# Placa_ATMEL_2019_v2.net
KiCad netlist of a schematic drawn in EAGLE
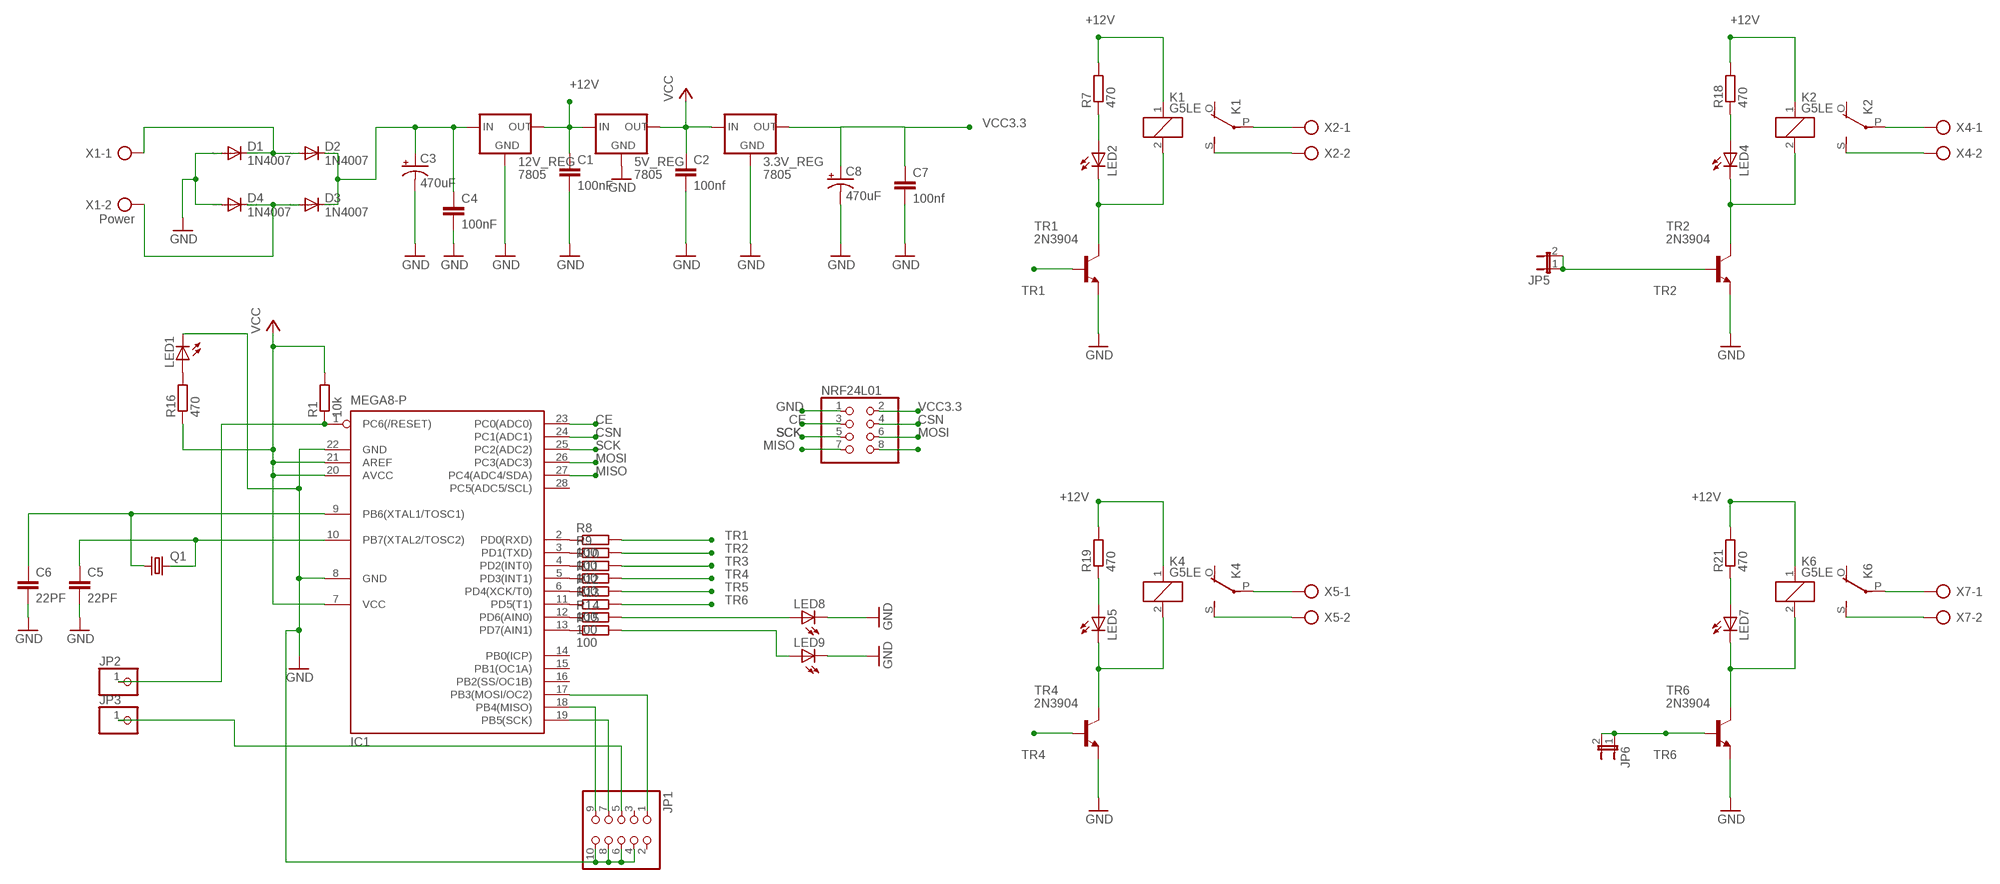
[diagram p0: schematic, sheet 1]

(export (version "E")
  (design (tool "Eeschema 10.0.6"))
  (components
    (comp (ref "3.3V_REG")
      (value "7805")
      (footprint "eagle-import:78XXL")
      (libsource (lib "eagle-import") (part "78XXL"))
    )
    (comp (ref "5V_REG")
      (value "7805")
      (footprint "eagle-import:78XXL")
      (libsource (lib "eagle-import") (part "78XXL"))
    )
    (comp (ref "12V_REG")
      (value "7805")
      (footprint "eagle-import:78XXL")
      (libsource (lib "eagle-import") (part "78XXL"))
    )
    (comp (ref "C1")
      (value "100nF")
      (footprint "eagle-import:C050-025X075")
      (libsource (lib "eagle-import") (part "C-EU050-025X075"))
    )
    (comp (ref "C2")
      (value "100nf")
      (footprint "eagle-import:C050-025X075")
      (libsource (lib "eagle-import") (part "C-EU050-025X075"))
    )
    (comp (ref "C3")
      (value "470uF")
      (footprint "eagle-import:E7,5-16")
      (libsource (lib "eagle-import") (part "CPOL-USE7.5-16"))
    )
    (comp (ref "C4")
      (value "100nF")
      (footprint "eagle-import:C050-025X075")
      (libsource (lib "eagle-import") (part "C-EU050-025X075"))
    )
    (comp (ref "C5")
      (value "22PF")
      (footprint "eagle-import:C050-024X044")
      (libsource (lib "eagle-import") (part "C-EU050-024X044"))
    )
    (comp (ref "C6")
      (value "22PF")
      (footprint "eagle-import:C050-024X044")
      (libsource (lib "eagle-import") (part "C-EU050-024X044"))
    )
    (comp (ref "C7")
      (value "100nf")
      (footprint "eagle-import:C050-025X075")
      (libsource (lib "eagle-import") (part "C-EU050-025X075"))
    )
    (comp (ref "C8")
      (value "470uF")
      (footprint "eagle-import:E7,5-16")
      (libsource (lib "eagle-import") (part "CPOL-USE7.5-16"))
    )
    (comp (ref "D1")
      (value "1N4007")
      (footprint "eagle-import:DO41-10")
      (libsource (lib "eagle-import") (part "1N4004"))
    )
    (comp (ref "D2")
      (value "1N4007")
      (footprint "eagle-import:DO41-10")
      (libsource (lib "eagle-import") (part "1N4004"))
    )
    (comp (ref "D3")
      (value "1N4007")
      (footprint "eagle-import:DO41-10")
      (libsource (lib "eagle-import") (part "1N4004"))
    )
    (comp (ref "D4")
      (value "1N4007")
      (footprint "eagle-import:DO41-10")
      (libsource (lib "eagle-import") (part "1N4004"))
    )
    (comp (ref "IC1")
      (value "MEGA8-P")
      (footprint "eagle-import:DIL28-3")
      (libsource (lib "eagle-import") (part "MEGA8-P"))
    )
    (comp (ref "JP1")
      (value "PINHD-2X5")
      (footprint "eagle-import:2X05")
      (libsource (lib "eagle-import") (part "PINHD-2X5"))
    )
    (comp (ref "JP2")
      (value "PINHD-1X1")
      (footprint "eagle-import:1X01")
      (libsource (lib "eagle-import") (part "PINHD-1X1"))
    )
    (comp (ref "JP3")
      (value "PINHD-1X1")
      (footprint "eagle-import:1X01")
      (libsource (lib "eagle-import") (part "PINHD-1X1"))
    )
    (comp (ref "JP5")
      (value "JP1E")
      (footprint "eagle-import:JP1")
      (libsource (lib "eagle-import") (part "JP1E"))
    )
    (comp (ref "JP6")
      (value "JP1E")
      (footprint "eagle-import:JP1")
      (libsource (lib "eagle-import") (part "JP1E"))
    )
    (comp (ref "K1")
      (value "G5LE")
      (footprint "eagle-import:G5LE")
      (libsource (lib "eagle-import") (part "G5LE"))
    )
    (comp (ref "K2")
      (value "G5LE")
      (footprint "eagle-import:G5LE")
      (libsource (lib "eagle-import") (part "G5LE"))
    )
    (comp (ref "K4")
      (value "G5LE")
      (footprint "eagle-import:G5LE")
      (libsource (lib "eagle-import") (part "G5LE"))
    )
    (comp (ref "K6")
      (value "G5LE")
      (footprint "eagle-import:G5LE")
      (libsource (lib "eagle-import") (part "G5LE"))
    )
    (comp (ref "LED1")
      (value "LED5MM")
      (footprint "eagle-import:LED5MM")
      (libsource (lib "eagle-import") (part "LED5MM"))
    )
    (comp (ref "LED2")
      (value "LED5MM")
      (footprint "eagle-import:LED5MM")
      (libsource (lib "eagle-import") (part "LED5MM"))
    )
    (comp (ref "LED4")
      (value "LED5MM")
      (footprint "eagle-import:LED5MM")
      (libsource (lib "eagle-import") (part "LED5MM"))
    )
    (comp (ref "LED5")
      (value "LED5MM")
      (footprint "eagle-import:LED5MM")
      (libsource (lib "eagle-import") (part "LED5MM"))
    )
    (comp (ref "LED7")
      (value "LED5MM")
      (footprint "eagle-import:LED5MM")
      (libsource (lib "eagle-import") (part "LED5MM"))
    )
    (comp (ref "LED8")
      (value "LED5MM")
      (footprint "eagle-import:LED5MM")
      (libsource (lib "eagle-import") (part "LED5MM"))
    )
    (comp (ref "LED9")
      (value "LED5MM")
      (footprint "eagle-import:LED5MM")
      (libsource (lib "eagle-import") (part "LED5MM"))
    )
    (comp (ref "NRF24L01")
      (value "PINHD-2X4")
      (footprint "eagle-import:2X04")
      (libsource (lib "eagle-import") (part "PINHD-2X4"))
    )
    (comp (ref "Q1")
      (value "CRYSTALHC49S")
      (footprint "eagle-import:HC49_S")
      (libsource (lib "eagle-import") (part "CRYSTALHC49S"))
    )
    (comp (ref "R1")
      (value "10k")
      (footprint "eagle-import:0207_10")
      (libsource (lib "eagle-import") (part "R-EU_0207/10"))
    )
    (comp (ref "R7")
      (value "470")
      (footprint "eagle-import:0309_10")
      (libsource (lib "eagle-import") (part "R-EU_0309/10"))
    )
    (comp (ref "R8")
      (value "100")
      (footprint "eagle-import:0207_10")
      (libsource (lib "eagle-import") (part "R-EU_0207/10"))
    )
    (comp (ref "R9")
      (value "100")
      (footprint "eagle-import:0207_10")
      (libsource (lib "eagle-import") (part "R-EU_0207/10"))
    )
    (comp (ref "R10")
      (value "100")
      (footprint "eagle-import:0207_15")
      (libsource (lib "eagle-import") (part "R-EU_0207/15"))
    )
    (comp (ref "R11")
      (value "100")
      (footprint "eagle-import:0207_10")
      (libsource (lib "eagle-import") (part "R-EU_0207/10"))
    )
    (comp (ref "R12")
      (value "R-EU_0207/15")
      (footprint "eagle-import:0207_15")
      (libsource (lib "eagle-import") (part "R-EU_0207/15"))
    )
    (comp (ref "R13")
      (value "100")
      (footprint "eagle-import:0207_15")
      (libsource (lib "eagle-import") (part "R-EU_0207/15"))
    )
    (comp (ref "R14")
      (value "100")
      (footprint "eagle-import:0207_10")
      (libsource (lib "eagle-import") (part "R-EU_0207/10"))
    )
    (comp (ref "R15")
      (value "100")
      (footprint "eagle-import:0207_10")
      (libsource (lib "eagle-import") (part "R-EU_0207/10"))
    )
    (comp (ref "R16")
      (value "470")
      (footprint "eagle-import:0309_10")
      (libsource (lib "eagle-import") (part "R-EU_0309/10"))
    )
    (comp (ref "R18")
      (value "470")
      (footprint "eagle-import:0309_10")
      (libsource (lib "eagle-import") (part "R-EU_0309/10"))
    )
    (comp (ref "R19")
      (value "470")
      (footprint "eagle-import:0309_10")
      (libsource (lib "eagle-import") (part "R-EU_0309/10"))
    )
    (comp (ref "R21")
      (value "470")
      (footprint "eagle-import:0309_10")
      (libsource (lib "eagle-import") (part "R-EU_0309/10"))
    )
    (comp (ref "TR1")
      (value "2N3904")
      (footprint "eagle-import:TO92")
      (libsource (lib "eagle-import") (part "2N3904"))
    )
    (comp (ref "TR2")
      (value "2N3904")
      (footprint "eagle-import:TO92")
      (libsource (lib "eagle-import") (part "2N3904"))
    )
    (comp (ref "TR4")
      (value "2N3904")
      (footprint "eagle-import:TO92")
      (libsource (lib "eagle-import") (part "2N3904"))
    )
    (comp (ref "TR6")
      (value "2N3904")
      (footprint "eagle-import:TO92")
      (libsource (lib "eagle-import") (part "2N3904"))
    )
    (comp (ref "X1")
      (value "Power")
      (footprint "eagle-import:AK500_2")
      (libsource (lib "eagle-import") (part "AK500/2"))
    )
    (comp (ref "X2")
      (value "AK300/2")
      (footprint "eagle-import:AK300_2")
      (libsource (lib "eagle-import") (part "AK300/2"))
    )
    (comp (ref "X4")
      (value "AK300/2")
      (footprint "eagle-import:AK300_2")
      (libsource (lib "eagle-import") (part "AK300/2"))
    )
    (comp (ref "X5")
      (value "AK300/2")
      (footprint "eagle-import:AK300_2")
      (libsource (lib "eagle-import") (part "AK300/2"))
    )
    (comp (ref "X7")
      (value "AK300/2")
      (footprint "eagle-import:AK300_2")
      (libsource (lib "eagle-import") (part "AK300/2"))
    )
  )
  (nets
    (net (code "1") (name "/+12V") (class "Default")
      (node (ref "12V_REG") (pin "OUT") (pinfunction "OUT_OUT") (pintype "passive"))
      (node (ref "5V_REG") (pin "IN") (pinfunction "IN_IN") (pintype "input"))
      (node (ref "C1") (pin "1") (pinfunction "1_1") (pintype "passive"))
      (node (ref "K1") (pin "1") (pinfunction "1_1") (pintype "passive"))
      (node (ref "K2") (pin "1") (pinfunction "1_1") (pintype "passive"))
      (node (ref "K4") (pin "1") (pinfunction "1_1") (pintype "passive"))
      (node (ref "K6") (pin "1") (pinfunction "1_1") (pintype "passive"))
      (node (ref "R18") (pin "2") (pinfunction "2_2") (pintype "passive"))
      (node (ref "R19") (pin "2") (pinfunction "2_2") (pintype "passive"))
      (node (ref "R21") (pin "2") (pinfunction "2_2") (pintype "passive"))
      (node (ref "R7") (pin "2") (pinfunction "2_2") (pintype "passive"))
    )
    (net (code "2") (name "/CE") (class "Default")
      (node (ref "IC1") (pin "23") (pinfunction "PC0(ADC0)_23") (pintype "bidirectional"))
      (node (ref "NRF24L01") (pin "3") (pinfunction "3_3") (pintype "passive"))
    )
    (net (code "3") (name "/CSN") (class "Default")
      (node (ref "IC1") (pin "24") (pinfunction "PC1(ADC1)_24") (pintype "bidirectional"))
      (node (ref "NRF24L01") (pin "4") (pinfunction "4_4") (pintype "passive"))
    )
    (net (code "4") (name "/MISO") (class "Default")
      (node (ref "IC1") (pin "27") (pinfunction "PC4(ADC4/SDA)_27") (pintype "bidirectional"))
      (node (ref "NRF24L01") (pin "7") (pinfunction "7_7") (pintype "passive"))
    )
    (net (code "5") (name "/MOSI") (class "Default")
      (node (ref "IC1") (pin "26") (pinfunction "PC3(ADC3)_26") (pintype "bidirectional"))
      (node (ref "NRF24L01") (pin "6") (pinfunction "6_6") (pintype "passive"))
    )
    (net (code "6") (name "/SCK") (class "Default")
      (node (ref "IC1") (pin "25") (pinfunction "PC2(ADC2)_25") (pintype "bidirectional"))
      (node (ref "NRF24L01") (pin "5") (pinfunction "5_5") (pintype "passive"))
    )
    (net (code "7") (name "/TR1") (class "Default")
      (node (ref "R8") (pin "2") (pinfunction "2_2") (pintype "passive"))
      (node (ref "TR1") (pin "2") (pinfunction "B_2") (pintype "passive"))
    )
    (net (code "8") (name "/TR2") (class "Default")
      (node (ref "JP5") (pin "1") (pinfunction "1_1") (pintype "passive"))
      (node (ref "JP5") (pin "2") (pinfunction "2_2") (pintype "passive"))
      (node (ref "R9") (pin "2") (pinfunction "2_2") (pintype "passive"))
      (node (ref "TR2") (pin "2") (pinfunction "B_2") (pintype "passive"))
    )
    (net (code "9") (name "/TR3") (class "Default")
      (node (ref "R10") (pin "2") (pinfunction "2_2") (pintype "passive"))
    )
    (net (code "10") (name "/TR4") (class "Default")
      (node (ref "R11") (pin "2") (pinfunction "2_2") (pintype "passive"))
      (node (ref "TR4") (pin "2") (pinfunction "B_2") (pintype "passive"))
    )
    (net (code "11") (name "/TR5") (class "Default")
      (node (ref "R12") (pin "2") (pinfunction "2_2") (pintype "passive"))
    )
    (net (code "12") (name "/TR6") (class "Default")
      (node (ref "JP6") (pin "1") (pinfunction "1_1") (pintype "passive"))
      (node (ref "JP6") (pin "2") (pinfunction "2_2") (pintype "passive"))
      (node (ref "R13") (pin "2") (pinfunction "2_2") (pintype "passive"))
      (node (ref "TR6") (pin "2") (pinfunction "B_2") (pintype "passive"))
    )
    (net (code "13") (name "/VCC3.3") (class "Default")
      (node (ref "3.3V_REG") (pin "OUT") (pinfunction "OUT_OUT") (pintype "passive"))
      (node (ref "C7") (pin "1") (pinfunction "1_1") (pintype "passive"))
      (node (ref "C8") (pin "+") (pinfunction "+_+") (pintype "passive"))
      (node (ref "NRF24L01") (pin "2") (pinfunction "2_2") (pintype "passive"))
    )
    (net (code "14") (name "GND") (class "Default")
      (node (ref "12V_REG") (pin "GND") (pinfunction "GND_GND") (pintype "input"))
      (node (ref "3.3V_REG") (pin "GND") (pinfunction "GND_GND") (pintype "input"))
      (node (ref "5V_REG") (pin "GND") (pinfunction "GND_GND") (pintype "input"))
      (node (ref "C1") (pin "2") (pinfunction "2_2") (pintype "passive"))
      (node (ref "C2") (pin "2") (pinfunction "2_2") (pintype "passive"))
      (node (ref "C3") (pin "-") (pinfunction "-_-") (pintype "passive"))
      (node (ref "C4") (pin "2") (pinfunction "2_2") (pintype "passive"))
      (node (ref "C5") (pin "2") (pinfunction "2_2") (pintype "passive"))
      (node (ref "C6") (pin "2") (pinfunction "2_2") (pintype "passive"))
      (node (ref "C7") (pin "2") (pinfunction "2_2") (pintype "passive"))
      (node (ref "C8") (pin "-") (pinfunction "-_-") (pintype "passive"))
      (node (ref "D1") (pin "A") (pinfunction "A_A") (pintype "passive"))
      (node (ref "D4") (pin "A") (pinfunction "A_A") (pintype "passive"))
      (node (ref "IC1") (pin "22") (pinfunction "GND_22") (pintype "power_in"))
      (node (ref "IC1") (pin "8") (pinfunction "GND_8") (pintype "power_in"))
      (node (ref "JP1") (pin "10") (pinfunction "10_10") (pintype "passive"))
      (node (ref "JP1") (pin "4") (pinfunction "4_4") (pintype "passive"))
      (node (ref "JP1") (pin "6") (pinfunction "6_6") (pintype "passive"))
      (node (ref "JP1") (pin "8") (pinfunction "8_8") (pintype "passive"))
      (node (ref "LED1") (pin "K") (pinfunction "C_K") (pintype "passive"))
      (node (ref "LED8") (pin "K") (pinfunction "C_K") (pintype "passive"))
      (node (ref "LED9") (pin "K") (pinfunction "C_K") (pintype "passive"))
      (node (ref "NRF24L01") (pin "1") (pinfunction "1_1") (pintype "passive"))
      (node (ref "TR1") (pin "3") (pinfunction "E_3") (pintype "passive"))
      (node (ref "TR2") (pin "3") (pinfunction "E_3") (pintype "passive"))
      (node (ref "TR4") (pin "3") (pinfunction "E_3") (pintype "passive"))
      (node (ref "TR6") (pin "3") (pinfunction "E_3") (pintype "passive"))
    )
    (net (code "15") (name "Net-(12V_REG-PadIN)") (class "Default")
      (node (ref "12V_REG") (pin "IN") (pinfunction "IN_IN") (pintype "input"))
      (node (ref "C3") (pin "+") (pinfunction "+_+") (pintype "passive"))
      (node (ref "C4") (pin "1") (pinfunction "1_1") (pintype "passive"))
      (node (ref "D2") (pin "C") (pinfunction "C_C") (pintype "passive"))
      (node (ref "D3") (pin "C") (pinfunction "C_C") (pintype "passive"))
    )
    (net (code "16") (name "Net-(IC1-PB3(MOSI{slash}OC2))") (class "Default")
      (node (ref "IC1") (pin "17") (pinfunction "PB3(MOSI/OC2)_17") (pintype "bidirectional"))
      (node (ref "JP1") (pin "1") (pinfunction "1_1") (pintype "passive"))
    )
    (net (code "17") (name "Net-(IC1-PB4(MISO))") (class "Default")
      (node (ref "IC1") (pin "18") (pinfunction "PB4(MISO)_18") (pintype "bidirectional"))
      (node (ref "JP1") (pin "9") (pinfunction "9_9") (pintype "passive"))
    )
    (net (code "18") (name "Net-(IC1-PB5(SCK))") (class "Default")
      (node (ref "IC1") (pin "19") (pinfunction "PB5(SCK)_19") (pintype "bidirectional"))
      (node (ref "JP1") (pin "7") (pinfunction "7_7") (pintype "passive"))
    )
    (net (code "19") (name "Net-(IC1-PB6(XTAL1{slash}TOSC1))") (class "Default")
      (node (ref "C6") (pin "1") (pinfunction "1_1") (pintype "passive"))
      (node (ref "IC1") (pin "9") (pinfunction "PB6(XTAL1/TOSC1)_9") (pintype "bidirectional"))
      (node (ref "Q1") (pin "1") (pinfunction "1_1") (pintype "passive"))
    )
    (net (code "20") (name "Net-(IC1-PB7(XTAL2{slash}TOSC2))") (class "Default")
      (node (ref "C5") (pin "1") (pinfunction "1_1") (pintype "passive"))
      (node (ref "IC1") (pin "10") (pinfunction "PB7(XTAL2/TOSC2)_10") (pintype "bidirectional"))
      (node (ref "Q1") (pin "2") (pinfunction "2_2") (pintype "passive"))
    )
    (net (code "21") (name "Net-(IC1-PC6({slash}RESET))") (class "Default")
      (node (ref "IC1") (pin "1") (pinfunction "PC6(/RESET)_1") (pintype "bidirectional"))
      (node (ref "JP2") (pin "1") (pinfunction "1_1") (pintype "passive"))
      (node (ref "R1") (pin "1") (pinfunction "1_1") (pintype "passive"))
    )
    (net (code "22") (name "Net-(IC1-PD0(RXD))") (class "Default")
      (node (ref "IC1") (pin "2") (pinfunction "PD0(RXD)_2") (pintype "bidirectional"))
      (node (ref "R8") (pin "1") (pinfunction "1_1") (pintype "passive"))
    )
    (net (code "23") (name "Net-(IC1-PD1(TXD))") (class "Default")
      (node (ref "IC1") (pin "3") (pinfunction "PD1(TXD)_3") (pintype "bidirectional"))
      (node (ref "R9") (pin "1") (pinfunction "1_1") (pintype "passive"))
    )
    (net (code "24") (name "Net-(IC1-PD2(INT0))") (class "Default")
      (node (ref "IC1") (pin "4") (pinfunction "PD2(INT0)_4") (pintype "bidirectional"))
      (node (ref "R10") (pin "1") (pinfunction "1_1") (pintype "passive"))
    )
    (net (code "25") (name "Net-(IC1-PD3(INT1))") (class "Default")
      (node (ref "IC1") (pin "5") (pinfunction "PD3(INT1)_5") (pintype "bidirectional"))
      (node (ref "R11") (pin "1") (pinfunction "1_1") (pintype "passive"))
    )
    (net (code "26") (name "Net-(IC1-PD4(XCK{slash}T0))") (class "Default")
      (node (ref "IC1") (pin "6") (pinfunction "PD4(XCK/T0)_6") (pintype "bidirectional"))
      (node (ref "R12") (pin "1") (pinfunction "1_1") (pintype "passive"))
    )
    (net (code "27") (name "Net-(IC1-PD5(T1))") (class "Default")
      (node (ref "IC1") (pin "11") (pinfunction "PD5(T1)_11") (pintype "bidirectional"))
      (node (ref "R13") (pin "1") (pinfunction "1_1") (pintype "passive"))
    )
    (net (code "28") (name "Net-(IC1-PD6(AIN0))") (class "Default")
      (node (ref "IC1") (pin "12") (pinfunction "PD6(AIN0)_12") (pintype "bidirectional"))
      (node (ref "R14") (pin "1") (pinfunction "1_1") (pintype "passive"))
    )
    (net (code "29") (name "Net-(IC1-PD7(AIN1))") (class "Default")
      (node (ref "IC1") (pin "13") (pinfunction "PD7(AIN1)_13") (pintype "bidirectional"))
      (node (ref "R15") (pin "1") (pinfunction "1_1") (pintype "passive"))
    )
    (net (code "30") (name "Net-(JP1-Pad5)") (class "Default")
      (node (ref "JP1") (pin "5") (pinfunction "5_5") (pintype "passive"))
      (node (ref "JP3") (pin "1") (pinfunction "1_1") (pintype "passive"))
    )
    (net (code "31") (name "Net-(LED1-PadA)") (class "Default")
      (node (ref "LED1") (pin "A") (pinfunction "A_A") (pintype "passive"))
      (node (ref "R16") (pin "2") (pinfunction "2_2") (pintype "passive"))
    )
    (net (code "32") (name "Net-(LED2-C)") (class "Default")
      (node (ref "K1") (pin "2") (pinfunction "2_2") (pintype "passive"))
      (node (ref "LED2") (pin "K") (pinfunction "C_K") (pintype "passive"))
      (node (ref "TR1") (pin "1") (pinfunction "C_1") (pintype "passive"))
    )
    (net (code "33") (name "Net-(LED2-PadA)") (class "Default")
      (node (ref "LED2") (pin "A") (pinfunction "A_A") (pintype "passive"))
      (node (ref "R7") (pin "1") (pinfunction "1_1") (pintype "passive"))
    )
    (net (code "34") (name "Net-(LED4-C)") (class "Default")
      (node (ref "K2") (pin "2") (pinfunction "2_2") (pintype "passive"))
      (node (ref "LED4") (pin "K") (pinfunction "C_K") (pintype "passive"))
      (node (ref "TR2") (pin "1") (pinfunction "C_1") (pintype "passive"))
    )
    (net (code "35") (name "Net-(LED4-PadA)") (class "Default")
      (node (ref "LED4") (pin "A") (pinfunction "A_A") (pintype "passive"))
      (node (ref "R18") (pin "1") (pinfunction "1_1") (pintype "passive"))
    )
    (net (code "36") (name "Net-(LED5-C)") (class "Default")
      (node (ref "K4") (pin "2") (pinfunction "2_2") (pintype "passive"))
      (node (ref "LED5") (pin "K") (pinfunction "C_K") (pintype "passive"))
      (node (ref "TR4") (pin "1") (pinfunction "C_1") (pintype "passive"))
    )
    (net (code "37") (name "Net-(LED5-PadA)") (class "Default")
      (node (ref "LED5") (pin "A") (pinfunction "A_A") (pintype "passive"))
      (node (ref "R19") (pin "1") (pinfunction "1_1") (pintype "passive"))
    )
    (net (code "38") (name "Net-(LED7-C)") (class "Default")
      (node (ref "K6") (pin "2") (pinfunction "2_2") (pintype "passive"))
      (node (ref "LED7") (pin "K") (pinfunction "C_K") (pintype "passive"))
      (node (ref "TR6") (pin "1") (pinfunction "C_1") (pintype "passive"))
    )
    (net (code "39") (name "Net-(LED7-PadA)") (class "Default")
      (node (ref "LED7") (pin "A") (pinfunction "A_A") (pintype "passive"))
      (node (ref "R21") (pin "1") (pinfunction "1_1") (pintype "passive"))
    )
    (net (code "40") (name "Net-(LED8-PadA)") (class "Default")
      (node (ref "LED8") (pin "A") (pinfunction "A_A") (pintype "passive"))
      (node (ref "R14") (pin "2") (pinfunction "2_2") (pintype "passive"))
    )
    (net (code "41") (name "Net-(LED9-PadA)") (class "Default")
      (node (ref "LED9") (pin "A") (pinfunction "A_A") (pintype "passive"))
      (node (ref "R15") (pin "2") (pinfunction "2_2") (pintype "passive"))
    )
    (net (code "42") (name "Net-(X1A-KL)") (class "Default")
      (node (ref "D1") (pin "C") (pinfunction "C_C") (pintype "passive"))
      (node (ref "D2") (pin "A") (pinfunction "A_A") (pintype "passive"))
      (node (ref "X1") (pin "1") (pinfunction "KL_1") (pintype "passive"))
    )
    (net (code "43") (name "Net-(X1B-KL)") (class "Default")
      (node (ref "D3") (pin "A") (pinfunction "A_A") (pintype "passive"))
      (node (ref "D4") (pin "C") (pinfunction "C_C") (pintype "passive"))
      (node (ref "X1") (pin "2") (pinfunction "KL_2") (pintype "passive"))
    )
    (net (code "44") (name "Net-(X2A-KL)") (class "Default")
      (node (ref "K1") (pin "P") (pinfunction "P_P") (pintype "passive"))
      (node (ref "X2") (pin "1") (pinfunction "KL_1") (pintype "passive"))
    )
    (net (code "45") (name "Net-(X2B-KL)") (class "Default")
      (node (ref "K1") (pin "S") (pinfunction "S_S") (pintype "passive"))
      (node (ref "X2") (pin "2") (pinfunction "KL_2") (pintype "passive"))
    )
    (net (code "46") (name "Net-(X4A-KL)") (class "Default")
      (node (ref "K2") (pin "P") (pinfunction "P_P") (pintype "passive"))
      (node (ref "X4") (pin "1") (pinfunction "KL_1") (pintype "passive"))
    )
    (net (code "47") (name "Net-(X4B-KL)") (class "Default")
      (node (ref "K2") (pin "S") (pinfunction "S_S") (pintype "passive"))
      (node (ref "X4") (pin "2") (pinfunction "KL_2") (pintype "passive"))
    )
    (net (code "48") (name "Net-(X5A-KL)") (class "Default")
      (node (ref "K4") (pin "P") (pinfunction "P_P") (pintype "passive"))
      (node (ref "X5") (pin "1") (pinfunction "KL_1") (pintype "passive"))
    )
    (net (code "49") (name "Net-(X5B-KL)") (class "Default")
      (node (ref "K4") (pin "S") (pinfunction "S_S") (pintype "passive"))
      (node (ref "X5") (pin "2") (pinfunction "KL_2") (pintype "passive"))
    )
    (net (code "50") (name "Net-(X7A-KL)") (class "Default")
      (node (ref "K6") (pin "P") (pinfunction "P_P") (pintype "passive"))
      (node (ref "X7") (pin "1") (pinfunction "KL_1") (pintype "passive"))
    )
    (net (code "51") (name "Net-(X7B-KL)") (class "Default")
      (node (ref "K6") (pin "S") (pinfunction "S_S") (pintype "passive"))
      (node (ref "X7") (pin "2") (pinfunction "KL_2") (pintype "passive"))
    )
    (net (code "52") (name "VCC") (class "Default")
      (node (ref "3.3V_REG") (pin "IN") (pinfunction "IN_IN") (pintype "input"))
      (node (ref "5V_REG") (pin "OUT") (pinfunction "OUT_OUT") (pintype "passive"))
      (node (ref "C2") (pin "1") (pinfunction "1_1") (pintype "passive"))
      (node (ref "IC1") (pin "20") (pinfunction "AVCC_20") (pintype "power_in"))
      (node (ref "IC1") (pin "21") (pinfunction "AREF_21") (pintype "passive"))
      (node (ref "IC1") (pin "7") (pinfunction "VCC_7") (pintype "power_in"))
      (node (ref "R1") (pin "2") (pinfunction "2_2") (pintype "passive"))
      (node (ref "R16") (pin "1") (pinfunction "1_1") (pintype "passive"))
    )
    (net (code "53") (name "unconnected-(IC1-PB0(ICP)-Pad14)") (class "Default")
      (node (ref "IC1") (pin "14") (pinfunction "PB0(ICP)_14") (pintype "bidirectional"))
    )
    (net (code "54") (name "unconnected-(IC1-PB1(OC1A)-Pad15)") (class "Default")
      (node (ref "IC1") (pin "15") (pinfunction "PB1(OC1A)_15") (pintype "bidirectional"))
    )
    (net (code "55") (name "unconnected-(IC1-PB2(SS{slash}OC1B)-Pad16)") (class "Default")
      (node (ref "IC1") (pin "16") (pinfunction "PB2(SS/OC1B)_16") (pintype "bidirectional"))
    )
    (net (code "56") (name "unconnected-(IC1-PC5(ADC5{slash}SCL)-Pad28)") (class "Default")
      (node (ref "IC1") (pin "28") (pinfunction "PC5(ADC5/SCL)_28") (pintype "bidirectional"))
    )
    (net (code "57") (name "unconnected-(JP1-Pad2)") (class "Default")
      (node (ref "JP1") (pin "2") (pinfunction "2_2") (pintype "passive"))
    )
    (net (code "58") (name "unconnected-(JP1-Pad3)") (class "Default")
      (node (ref "JP1") (pin "3") (pinfunction "3_3") (pintype "passive"))
    )
    (net (code "59") (name "unconnected-(K1-PadO)") (class "Default")
      (node (ref "K1") (pin "O") (pinfunction "O_O") (pintype "passive"))
    )
    (net (code "60") (name "unconnected-(K2-PadO)") (class "Default")
      (node (ref "K2") (pin "O") (pinfunction "O_O") (pintype "passive"))
    )
    (net (code "61") (name "unconnected-(K4-PadO)") (class "Default")
      (node (ref "K4") (pin "O") (pinfunction "O_O") (pintype "passive"))
    )
    (net (code "62") (name "unconnected-(K6-PadO)") (class "Default")
      (node (ref "K6") (pin "O") (pinfunction "O_O") (pintype "passive"))
    )
    (net (code "63") (name "unconnected-(NRF24L01-Pad8)") (class "Default")
      (node (ref "NRF24L01") (pin "8") (pinfunction "8_8") (pintype "passive"))
    )
  )
)
